# Digitalizaci_n.net
KiCad netlist of a schematic drawn in Altium Designer
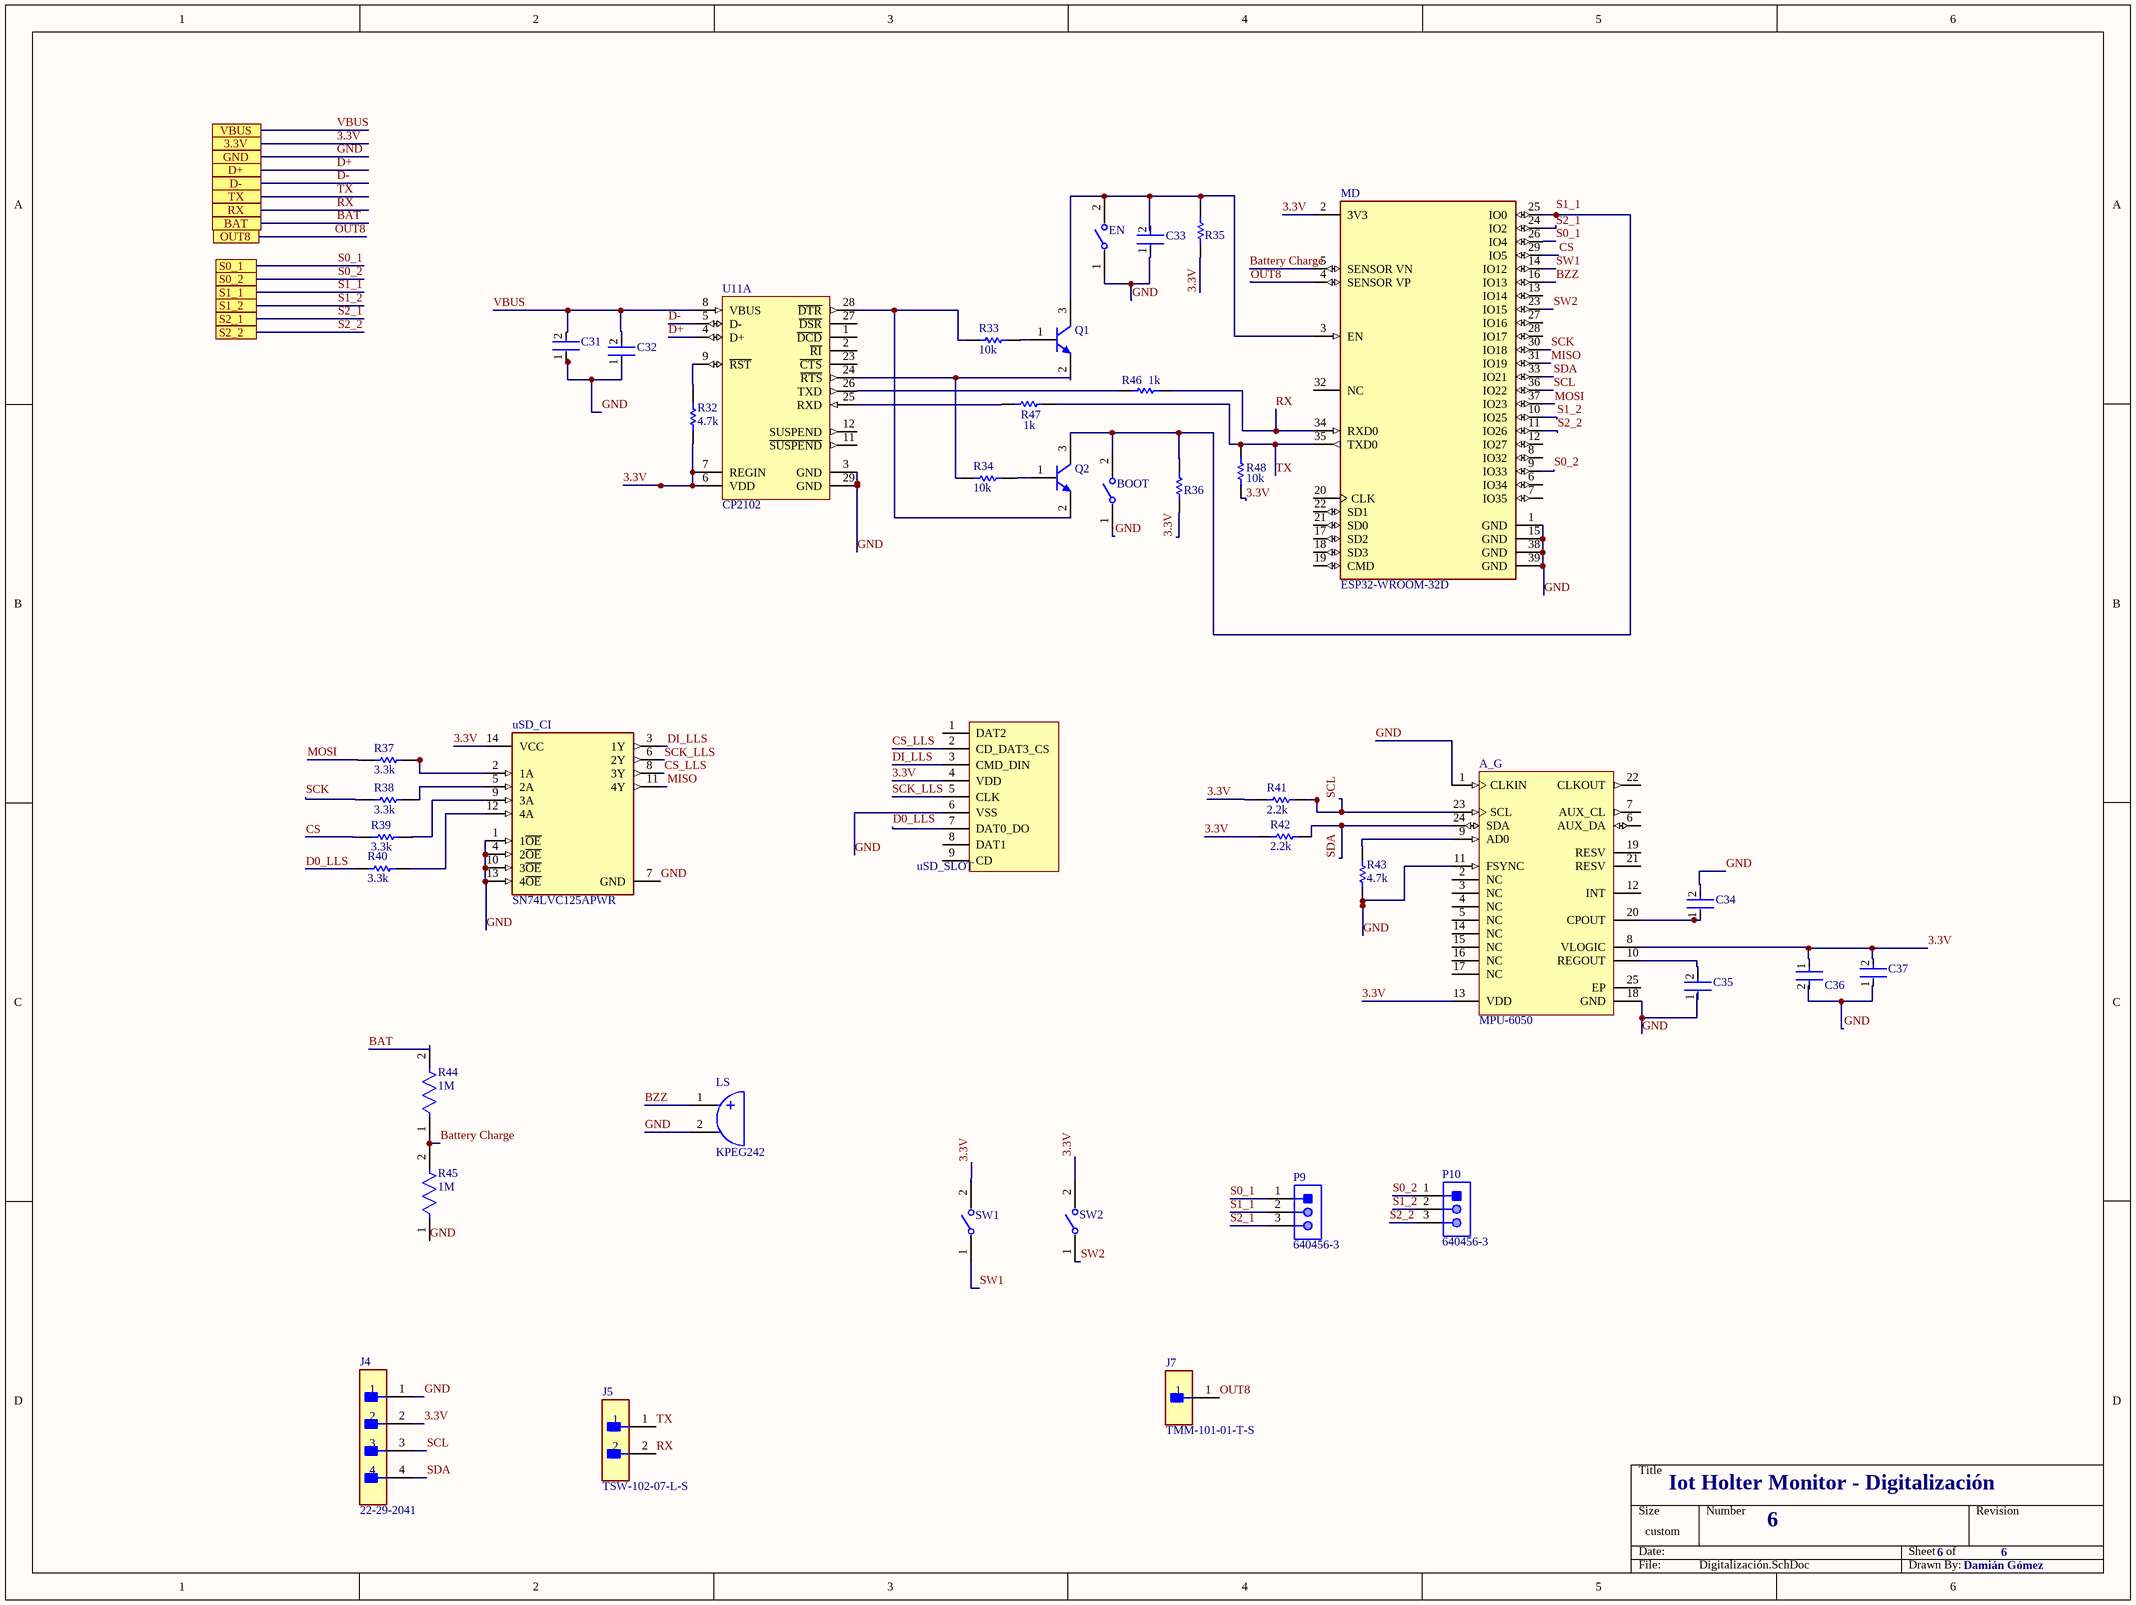
[diagram p0: Digitalización.SchDoc]

(export (version "E")
  (design (tool "Eeschema 10.0.6"))
  (components
    (comp (ref "A_G")
      (value "MPU-6050")
      (footprint "IS-QFN-24_V")
      (fields (field (name "MANUFACTURER") "InvenSense"))
      (libsource (lib "Altium Content Vault") (part "IS-MPU-6050-QFN-24"))
    )
    (comp (ref "BOOT")
      (value "B3U-1000P")
      (footprint "FP-B3U-1000P-MFG")
      (description "SWITCH TACTILE SPST-NO 0.05A 12V")
      (libsource (lib "Altium Content Vault") (part "ae622034201233ca1abcedc05908f33"))
    )
    (comp (ref "C31")
      (value "GRM2165C1H332JA01D")
      (footprint "FP-GRM216-0_1-IPC_B")
      (description "Chip Multilayer Ceramic Capacitors for General Purpose, 0805, 3300pF, C0G, 30ppm/°C, 5%, 50V")
      (fields (field (name "VOLTAGE") "50V") (field (name "TOLERANCE") "5%"))
      (libsource (lib "Altium Content Vault") (part "236180d848d6139a670b325ea6854c9"))
    )
    (comp (ref "C32")
      (value "GRM2165C1H332JA01D")
      (footprint "FP-GRM216-0_1-IPC_B")
      (description "Chip Multilayer Ceramic Capacitors for General Purpose, 0805, 3300pF, C0G, 30ppm/°C, 5%, 50V")
      (fields (field (name "VOLTAGE") "50V") (field (name "TOLERANCE") "5%"))
      (libsource (lib "Altium Content Vault") (part "236180d848d6139a670b325ea6854c9"))
    )
    (comp (ref "C33")
      (value "GRM2165C1H332JA01D")
      (footprint "FP-GRM216-0_1-IPC_B")
      (description "Chip Multilayer Ceramic Capacitors for General Purpose, 0805, 3300pF, C0G, 30ppm/°C, 5%, 50V")
      (fields (field (name "VOLTAGE") "50V") (field (name "TOLERANCE") "5%"))
      (libsource (lib "Altium Content Vault") (part "236180d848d6139a670b325ea6854c9"))
    )
    (comp (ref "C34")
      (value "GRM2165C1H332JA01D")
      (footprint "FP-GRM216-0_1-IPC_B")
      (description "Chip Multilayer Ceramic Capacitors for General Purpose, 0805, 3300pF, C0G, 30ppm/°C, 5%, 50V")
      (fields (field (name "VOLTAGE") "50V") (field (name "TOLERANCE") "5%"))
      (libsource (lib "Altium Content Vault") (part "236180d848d6139a670b325ea6854c9"))
    )
    (comp (ref "C35")
      (value "GRM2165C1H332JA01D")
      (footprint "FP-GRM216-0_1-IPC_B")
      (description "Chip Multilayer Ceramic Capacitors for General Purpose, 0805, 3300pF, C0G, 30ppm/°C, 5%, 50V")
      (fields (field (name "VOLTAGE") "50V") (field (name "TOLERANCE") "5%"))
      (libsource (lib "Altium Content Vault") (part "236180d848d6139a670b325ea6854c9"))
    )
    (comp (ref "C36")
      (value "10uF")
      (footprint "FP-CL31-IPC_C")
      (description "Cap Ceramic 10uF 500V C0G ±5% SMD 1206 +125°C Embossed T/R")
      (fields (field (name "TOLERANCE") "5%"))
      (libsource (lib "Altium Content Vault") (part "b4654b650e69147ec39a6b967a45e02"))
    )
    (comp (ref "C37")
      (value "GRM2165C1H332JA01D")
      (footprint "FP-GRM216-0_1-IPC_B")
      (description "Chip Multilayer Ceramic Capacitors for General Purpose, 0805, 3300pF, C0G, 30ppm/°C, 5%, 50V")
      (fields (field (name "VOLTAGE") "50V") (field (name "TOLERANCE") "5%"))
      (libsource (lib "Altium Content Vault") (part "236180d848d6139a670b325ea6854c9"))
    )
    (comp (ref "EN")
      (value "B3U-1000P")
      (footprint "FP-B3U-1000P-MFG")
      (description "SWITCH TACTILE SPST-NO 0.05A 12V")
      (libsource (lib "Altium Content Vault") (part "ae622034201233ca1abcedc05908f33"))
    )
    (comp (ref "J4")
      (value "22-29-2041")
      (footprint "FP-22-29-2041-MFG")
      (description "CONN HEADER VERT 4POS 2.54MM")
      (libsource (lib "Altium Content Vault") (part "299a8cea1bdcbc3624fe62c390fa72c"))
    )
    (comp (ref "J5")
      (value "TSW-102-07-L-S")
      (footprint "FP-TSW-102-07-L-S-MFG")
      (description "CONN HEADER VERT 2POS 2.54MM")
      (libsource (lib "Altium Content Vault") (part "3bc925449376181038e59eaffc5286c"))
    )
    (comp (ref "J7")
      (value "TMM-101-01-T-S")
      (footprint "FP-TMM-101-01-T-S-MFG")
      (description "CONN HEADER VERT 1POS")
      (libsource (lib "Altium Content Vault") (part "dd45045ce8184df9e99e12baf3f412c"))
    )
    (comp (ref "LS")
      (value "KPEG242")
      (footprint "KINGS-KPEG242-2")
      (description "Piezo Indicator, 4100 Hz, 3 to 16 V, -20 to 70 degC, 2-Pin THD, RoHS")
      (fields (field (name "PARTNUMBER") "KPE-242") (field (name "MANUFACTURER") "KingstateElectronicsCorp."))
      (libsource (lib "Altium Content Vault") (part "KINGS-KPEG242-2"))
    )
    (comp (ref "MD")
      (value "ESP32-WROOM-32D")
      (footprint "FP-ESP32-WROOM-32D-MFG")
      (description "WIFI MODULE 32MBITS SPI FLASH")
      (fields
        (field (name "OCTOPART") "https://octopart.com/esp32-wroom-32d-espressif+systems-91040050")
        (field (name "MANUFACTURER") "Espressif Systems")
      )
      (libsource (lib "Altium Content Vault") (part "a031a76f8c27026a7a7f4657ff233a3"))
    )
    (comp (ref "P9")
      (value "640456-3")
      (footprint "TECO-640456-3")
      (description "Male Header, Pitch 2.54 mm, 1 x 3 Position, Height 10.03 mm, Tail Length 3.56 mm, -55 to 105 degC")
      (fields (field (name "MANUFACTURER") "TE Connectivity"))
      (libsource (lib "Altium Content Vault") (part "CN-1P-M-R3"))
    )
    (comp (ref "P10")
      (value "640456-3")
      (footprint "TECO-640456-3")
      (description "Male Header, Pitch 2.54 mm, 1 x 3 Position, Height 10.03 mm, Tail Length 3.56 mm, -55 to 105 degC")
      (fields (field (name "MANUFACTURER") "TE Connectivity"))
      (libsource (lib "Altium Content Vault") (part "CN-1P-M-R3"))
    )
    (comp (ref "Q1")
      (value "MMBTA42LT1G")
      (footprint "ONSC-SOT-23-3-318-08_V")
      (description "High Voltage Transistor, NPN Silicon, 3-Pin SOT-23, Pb-Free, Tape and Reel")
      (fields (field (name "MANUFACTURER") "On Semiconductor"))
      (libsource (lib "Altium Content Vault") (part "ONSC-NPN-B1E2C3-3"))
    )
    (comp (ref "Q2")
      (value "MMBTA42LT1G")
      (footprint "ONSC-SOT-23-3-318-08_V")
      (description "High Voltage Transistor, NPN Silicon, 3-Pin SOT-23, Pb-Free, Tape and Reel")
      (fields (field (name "MANUFACTURER") "On Semiconductor"))
      (libsource (lib "Altium Content Vault") (part "ONSC-NPN-B1E2C3-3"))
    )
    (comp (ref "R32")
      (value "4.7k")
      (footprint "RESC2013X50X30LL20T20")
      (fields (field (name "MANUFACTURER") "Vishay Dale") (field (name "PART NUMBER") "CRCW08050000Z0EA"))
      (libsource (lib "Altium Content Vault") (part "RES"))
    )
    (comp (ref "R33")
      (value "10k")
      (footprint "RESC2013X50X30LL20T20")
      (fields (field (name "MANUFACTURER") "Vishay Dale") (field (name "PART NUMBER") "CRCW08050000Z0EA"))
      (libsource (lib "Altium Content Vault") (part "RES"))
    )
    (comp (ref "R34")
      (value "10k")
      (footprint "RESC2013X50X30LL20T20")
      (fields (field (name "MANUFACTURER") "Vishay Dale") (field (name "PART NUMBER") "CRCW08050000Z0EA"))
      (libsource (lib "Altium Content Vault") (part "RES"))
    )
    (comp (ref "R35")
      (value "10k")
      (footprint "RESC2013X50X30LL20T20")
      (fields (field (name "MANUFACTURER") "Vishay Dale") (field (name "PART NUMBER") "CRCW08050000Z0EA"))
      (libsource (lib "Altium Content Vault") (part "RES"))
    )
    (comp (ref "R36")
      (value "10k")
      (footprint "RESC2013X50X30LL20T20")
      (fields (field (name "MANUFACTURER") "Vishay Dale") (field (name "PART NUMBER") "CRCW08050000Z0EA"))
      (libsource (lib "Altium Content Vault") (part "RES"))
    )
    (comp (ref "R37")
      (value "3.3k")
      (footprint "RESC2013X50X30LL20T20")
      (fields (field (name "MANUFACTURER") "Vishay Dale") (field (name "PART NUMBER") "CRCW08050000Z0EA"))
      (libsource (lib "Altium Content Vault") (part "RES"))
    )
    (comp (ref "R38")
      (value "3.3k")
      (footprint "RESC2013X50X30LL20T20")
      (fields (field (name "MANUFACTURER") "Vishay Dale") (field (name "PART NUMBER") "CRCW08050000Z0EA"))
      (libsource (lib "Altium Content Vault") (part "RES"))
    )
    (comp (ref "R39")
      (value "3.3k")
      (footprint "RESC2013X50X30LL20T20")
      (fields (field (name "MANUFACTURER") "Vishay Dale") (field (name "PART NUMBER") "CRCW08050000Z0EA"))
      (libsource (lib "Altium Content Vault") (part "RES"))
    )
    (comp (ref "R40")
      (value "3.3k")
      (footprint "RESC2013X50X30LL20T20")
      (fields (field (name "MANUFACTURER") "Vishay Dale") (field (name "PART NUMBER") "CRCW08050000Z0EA"))
      (libsource (lib "Altium Content Vault") (part "RES"))
    )
    (comp (ref "R41")
      (value "2.2k")
      (footprint "RESC2013X50X30LL20T20")
      (fields (field (name "MANUFACTURER") "Vishay Dale") (field (name "PART NUMBER") "CRCW08050000Z0EA"))
      (libsource (lib "Altium Content Vault") (part "RES"))
    )
    (comp (ref "R42")
      (value "2.2k")
      (footprint "RESC2013X50X30LL20T20")
      (fields (field (name "MANUFACTURER") "Vishay Dale") (field (name "PART NUMBER") "CRCW08050000Z0EA"))
      (libsource (lib "Altium Content Vault") (part "RES"))
    )
    (comp (ref "R43")
      (value "4.7k")
      (footprint "RESC2013X50X30LL20T20")
      (fields (field (name "MANUFACTURER") "Vishay Dale") (field (name "PART NUMBER") "CRCW08050000Z0EA"))
      (libsource (lib "Altium Content Vault") (part "RES"))
    )
    (comp (ref "R44")
      (value "1M")
      (footprint "FP-RC3216-MFG")
      (description "Res Thick Film 1206 20kΩ 5% 0.25W ±100ppm/°C Molded SMD T/R")
      (fields (field (name "TOLERANCE") "5%"))
      (libsource (lib "Altium Content Vault") (part "1029c3af85768c4190bb7ad29bc67b5"))
    )
    (comp (ref "R45")
      (value "1M")
      (footprint "FP-RC3216-MFG")
      (description "Res Thick Film 1206 20kΩ 5% 0.25W ±100ppm/°C Molded SMD T/R")
      (fields (field (name "TOLERANCE") "5%"))
      (libsource (lib "Altium Content Vault") (part "1029c3af85768c4190bb7ad29bc67b5"))
    )
    (comp (ref "R46")
      (value "1k")
      (footprint "RESC2013X50X30LL20T20")
      (fields (field (name "MANUFACTURER") "Vishay Dale") (field (name "PART NUMBER") "CRCW08050000Z0EA"))
      (libsource (lib "Altium Content Vault") (part "RES"))
    )
    (comp (ref "R47")
      (value "1k")
      (footprint "RESC2013X50X30LL20T20")
      (fields (field (name "MANUFACTURER") "Vishay Dale") (field (name "PART NUMBER") "CRCW08050000Z0EA"))
      (libsource (lib "Altium Content Vault") (part "RES"))
    )
    (comp (ref "R48")
      (value "10k")
      (footprint "RESC2013X50X30LL20T20")
      (fields (field (name "MANUFACTURER") "Vishay Dale") (field (name "PART NUMBER") "CRCW08050000Z0EA"))
      (libsource (lib "Altium Content Vault") (part "RES"))
    )
    (comp (ref "SW1")
      (value "B3U-1000P")
      (footprint "FP-B3U-1000P-MFG")
      (description "SWITCH TACTILE SPST-NO 0.05A 12V")
      (libsource (lib "Altium Content Vault") (part "ae622034201233ca1abcedc05908f33"))
    )
    (comp (ref "SW2")
      (value "B3U-1000P")
      (footprint "FP-B3U-1000P-MFG")
      (description "SWITCH TACTILE SPST-NO 0.05A 12V")
      (libsource (lib "Altium Content Vault") (part "ae622034201233ca1abcedc05908f33"))
    )
    (comp (ref "U11")
      (value "CP2102")
      (footprint "SLAB-QFN-28-3125x3125TP_M")
      (description "Single-Chip USB to URAT Bridge, 3.3 V, -40 to 85 degC, 28-Pin QFN, RoHS, Tape and Reel")
      (fields (field (name "MANUFACTURER") "Silicon Labs"))
      (libsource (lib "Altium Content Vault") (part "SLAB-CP210X-QFN-28-29"))
    )
    (comp (ref "uSD_CI")
      (value "SN74LVC125APWR")
      (footprint "FP-PW0014A-IPC_B")
      (description "IC BUF NON-INVERT 3.6V 14TSSOP")
      (libsource (lib "Altium Content Vault") (part "0c185306b27c65c3e4a0d950f37c68a"))
    )
    (comp (ref "uSD_SLOT")
      (value "uSD_TFP09-2-12BComponent_1")
      (footprint "TF09-2-12B")
      (libsource (lib "uSD_TFP09-2-12B") (part "uSD_TFP09-2-12BComponent_1"))
    )
  )
  (nets
    (net (code "1") (name "/3.3V") (class "Default")
      (node (ref "A_G") (pin "13") (pinfunction "VDD_13") (pintype "power_in"))
      (node (ref "A_G") (pin "8") (pinfunction "VLOGIC_8") (pintype "power_in"))
      (node (ref "C36") (pin "1") (pinfunction "1_1") (pintype "passive"))
      (node (ref "C37") (pin "2") (pinfunction "2_2") (pintype "passive"))
      (node (ref "J4") (pin "2") (pinfunction "2_2") (pintype "passive"))
      (node (ref "MD") (pin "2") (pinfunction "3V3_2") (pintype "power_in"))
      (node (ref "R32") (pin "1") (pinfunction "1_1") (pintype "passive"))
      (node (ref "R35") (pin "1") (pinfunction "1_1") (pintype "passive"))
      (node (ref "R36") (pin "1") (pinfunction "1_1") (pintype "passive"))
      (node (ref "R41") (pin "1") (pinfunction "1_1") (pintype "passive"))
      (node (ref "R42") (pin "1") (pinfunction "1_1") (pintype "passive"))
      (node (ref "R48") (pin "1") (pinfunction "1_1") (pintype "passive"))
      (node (ref "SW1") (pin "2") (pinfunction "2_2") (pintype "passive"))
      (node (ref "SW2") (pin "2") (pinfunction "2_2") (pintype "passive"))
      (node (ref "U11") (pin "6") (pinfunction "VDD_6") (pintype "power_in"))
      (node (ref "U11") (pin "7") (pinfunction "REGIN_7") (pintype "power_in"))
      (node (ref "uSD_CI") (pin "14") (pinfunction "VCC_14") (pintype "power_in"))
      (node (ref "uSD_SLOT") (pin "4") (pinfunction "VDD_4") (pintype "passive"))
    )
    (net (code "2") (name "/BAT") (class "Default")
      (node (ref "R44") (pin "2") (pinfunction "2_2") (pintype "passive"))
    )
    (net (code "3") (name "/BZZ") (class "Default")
      (node (ref "LS") (pin "1") (pinfunction "1_1") (pintype "passive"))
      (node (ref "MD") (pin "16") (pinfunction "IO13_16") (pintype "bidirectional"))
    )
    (net (code "4") (name "/Battery Charge") (class "Default")
      (node (ref "MD") (pin "5") (pinfunction "SENSOR_VN_5") (pintype "bidirectional"))
      (node (ref "R44") (pin "1") (pinfunction "1_1") (pintype "passive"))
      (node (ref "R45") (pin "2") (pinfunction "2_2") (pintype "passive"))
    )
    (net (code "5") (name "/CS") (class "Default")
      (node (ref "MD") (pin "29") (pinfunction "IO5_29") (pintype "bidirectional"))
      (node (ref "R39") (pin "1") (pinfunction "1_1") (pintype "passive"))
    )
    (net (code "6") (name "/CS_LLS") (class "Default")
      (node (ref "uSD_CI") (pin "8") (pinfunction "3Y_8") (pintype "output"))
      (node (ref "uSD_SLOT") (pin "2") (pinfunction "CD_DAT3_CS_2") (pintype "passive"))
    )
    (net (code "7") (name "/D+") (class "Default")
      (node (ref "U11") (pin "4") (pinfunction "D+_4") (pintype "bidirectional"))
    )
    (net (code "8") (name "/D-") (class "Default")
      (node (ref "U11") (pin "5") (pinfunction "D-_5") (pintype "bidirectional"))
    )
    (net (code "9") (name "/D0_LLS") (class "Default")
      (node (ref "R40") (pin "1") (pinfunction "1_1") (pintype "passive"))
      (node (ref "uSD_SLOT") (pin "7") (pinfunction "DAT0_DO_7") (pintype "passive"))
    )
    (net (code "10") (name "/DI_LLS") (class "Default")
      (node (ref "uSD_CI") (pin "3") (pinfunction "1Y_3") (pintype "output"))
      (node (ref "uSD_SLOT") (pin "3") (pinfunction "CMD_DIN_3") (pintype "passive"))
    )
    (net (code "11") (name "/GND") (class "Default")
      (node (ref "A_G") (pin "1") (pinfunction "CLKIN_1") (pintype "input"))
      (node (ref "A_G") (pin "11") (pinfunction "FSYNC_11") (pintype "input"))
      (node (ref "A_G") (pin "18") (pinfunction "GND_18") (pintype "passive"))
      (node (ref "BOOT") (pin "1") (pinfunction "1_1") (pintype "passive"))
      (node (ref "C31") (pin "1") (pinfunction "1_1") (pintype "passive"))
      (node (ref "C32") (pin "1") (pinfunction "1_1") (pintype "passive"))
      (node (ref "C33") (pin "1") (pinfunction "1_1") (pintype "passive"))
      (node (ref "C34") (pin "2") (pinfunction "2_2") (pintype "passive"))
      (node (ref "C35") (pin "1") (pinfunction "1_1") (pintype "passive"))
      (node (ref "C36") (pin "2") (pinfunction "2_2") (pintype "passive"))
      (node (ref "C37") (pin "1") (pinfunction "1_1") (pintype "passive"))
      (node (ref "EN") (pin "1") (pinfunction "1_1") (pintype "passive"))
      (node (ref "J4") (pin "1") (pinfunction "1_1") (pintype "passive"))
      (node (ref "LS") (pin "2") (pinfunction "2_2") (pintype "passive"))
      (node (ref "MD") (pin "1") (pinfunction "GND_1") (pintype "passive"))
      (node (ref "MD") (pin "15") (pinfunction "GND_15") (pintype "passive"))
      (node (ref "MD") (pin "38") (pinfunction "GND_38") (pintype "passive"))
      (node (ref "MD") (pin "39") (pinfunction "GND_39") (pintype "passive"))
      (node (ref "R43") (pin "1") (pinfunction "1_1") (pintype "passive"))
      (node (ref "R45") (pin "1") (pinfunction "1_1") (pintype "passive"))
      (node (ref "U11") (pin "29") (pinfunction "GND_29") (pintype "passive"))
      (node (ref "U11") (pin "3") (pinfunction "GND_3") (pintype "passive"))
      (node (ref "uSD_CI") (pin "1") (pinfunction "1~{OE}_1") (pintype "input"))
      (node (ref "uSD_CI") (pin "10") (pinfunction "3~{OE}_10") (pintype "input"))
      (node (ref "uSD_CI") (pin "13") (pinfunction "4~{OE}_13") (pintype "input"))
      (node (ref "uSD_CI") (pin "4") (pinfunction "2~{OE}_4") (pintype "input"))
      (node (ref "uSD_CI") (pin "7") (pinfunction "GND_7") (pintype "passive"))
      (node (ref "uSD_SLOT") (pin "6") (pinfunction "VSS_6") (pintype "passive"))
    )
    (net (code "12") (name "/MISO") (class "Default")
      (node (ref "MD") (pin "31") (pinfunction "IO19_31") (pintype "bidirectional"))
      (node (ref "uSD_CI") (pin "11") (pinfunction "4Y_11") (pintype "output"))
    )
    (net (code "13") (name "/MOSI") (class "Default")
      (node (ref "MD") (pin "37") (pinfunction "IO23_37") (pintype "bidirectional"))
      (node (ref "R37") (pin "1") (pinfunction "1_1") (pintype "passive"))
    )
    (net (code "14") (name "/OUT8") (class "Default")
      (node (ref "J7") (pin "1") (pinfunction "1_1") (pintype "passive"))
      (node (ref "MD") (pin "4") (pinfunction "SENSOR_VP_4") (pintype "bidirectional"))
    )
    (net (code "15") (name "/RX") (class "Default")
      (node (ref "J5") (pin "2") (pinfunction "2_2") (pintype "passive"))
      (node (ref "MD") (pin "34") (pinfunction "RXD0_34") (pintype "input"))
      (node (ref "R46") (pin "2") (pinfunction "2_2") (pintype "passive"))
    )
    (net (code "16") (name "/S0_1") (class "Default")
      (node (ref "MD") (pin "26") (pinfunction "IO4_26") (pintype "bidirectional"))
      (node (ref "P9") (pin "1") (pinfunction "1_1") (pintype "passive"))
    )
    (net (code "17") (name "/S0_2") (class "Default")
      (node (ref "MD") (pin "9") (pinfunction "IO33_9") (pintype "bidirectional"))
      (node (ref "P10") (pin "1") (pinfunction "1_1") (pintype "passive"))
    )
    (net (code "18") (name "/S1_1") (class "Default")
      (node (ref "BOOT") (pin "2") (pinfunction "2_2") (pintype "passive"))
      (node (ref "MD") (pin "25") (pinfunction "IO0_25") (pintype "bidirectional"))
      (node (ref "P9") (pin "2") (pinfunction "2_2") (pintype "passive"))
      (node (ref "Q2") (pin "3") (pinfunction "C_3") (pintype "passive"))
      (node (ref "R36") (pin "2") (pinfunction "2_2") (pintype "passive"))
    )
    (net (code "19") (name "/S1_2") (class "Default")
      (node (ref "MD") (pin "10") (pinfunction "IO25_10") (pintype "bidirectional"))
      (node (ref "P10") (pin "2") (pinfunction "2_2") (pintype "passive"))
    )
    (net (code "20") (name "/S2_1") (class "Default")
      (node (ref "MD") (pin "24") (pinfunction "IO2_24") (pintype "bidirectional"))
      (node (ref "P9") (pin "3") (pinfunction "3_3") (pintype "passive"))
    )
    (net (code "21") (name "/S2_2") (class "Default")
      (node (ref "MD") (pin "11") (pinfunction "IO26_11") (pintype "bidirectional"))
      (node (ref "P10") (pin "3") (pinfunction "3_3") (pintype "passive"))
    )
    (net (code "22") (name "/SCK") (class "Default")
      (node (ref "MD") (pin "30") (pinfunction "IO18_30") (pintype "bidirectional"))
      (node (ref "R38") (pin "1") (pinfunction "1_1") (pintype "passive"))
    )
    (net (code "23") (name "/SCK_LLS") (class "Default")
      (node (ref "uSD_CI") (pin "6") (pinfunction "2Y_6") (pintype "output"))
      (node (ref "uSD_SLOT") (pin "5") (pinfunction "CLK_5") (pintype "passive"))
    )
    (net (code "24") (name "/SCL") (class "Default")
      (node (ref "A_G") (pin "23") (pinfunction "SCL_23") (pintype "input"))
      (node (ref "J4") (pin "3") (pinfunction "3_3") (pintype "passive"))
      (node (ref "MD") (pin "36") (pinfunction "IO22_36") (pintype "bidirectional"))
      (node (ref "R41") (pin "2") (pinfunction "2_2") (pintype "passive"))
    )
    (net (code "25") (name "/SDA") (class "Default")
      (node (ref "A_G") (pin "24") (pinfunction "SDA_24") (pintype "bidirectional"))
      (node (ref "J4") (pin "4") (pinfunction "4_4") (pintype "passive"))
      (node (ref "MD") (pin "33") (pinfunction "IO21_33") (pintype "bidirectional"))
      (node (ref "R42") (pin "2") (pinfunction "2_2") (pintype "passive"))
    )
    (net (code "26") (name "/SW1") (class "Default")
      (node (ref "MD") (pin "14") (pinfunction "IO12_14") (pintype "bidirectional"))
      (node (ref "SW1") (pin "1") (pinfunction "1_1") (pintype "passive"))
    )
    (net (code "27") (name "/SW2") (class "Default")
      (node (ref "MD") (pin "23") (pinfunction "IO15_23") (pintype "bidirectional"))
      (node (ref "SW2") (pin "1") (pinfunction "1_1") (pintype "passive"))
    )
    (net (code "28") (name "/TX") (class "Default")
      (node (ref "J5") (pin "1") (pinfunction "1_1") (pintype "passive"))
      (node (ref "MD") (pin "35") (pinfunction "TXD0_35") (pintype "output"))
      (node (ref "R47") (pin "2") (pinfunction "2_2") (pintype "passive"))
      (node (ref "R48") (pin "2") (pinfunction "2_2") (pintype "passive"))
    )
    (net (code "29") (name "/VBUS") (class "Default")
      (node (ref "C31") (pin "2") (pinfunction "2_2") (pintype "passive"))
      (node (ref "C32") (pin "2") (pinfunction "2_2") (pintype "passive"))
      (node (ref "U11") (pin "8") (pinfunction "VBUS_8") (pintype "input"))
    )
    (net (code "30") (name "Net-(A_G-AD0)") (class "Default")
      (node (ref "A_G") (pin "9") (pinfunction "AD0_9") (pintype "input"))
      (node (ref "R43") (pin "2") (pinfunction "2_2") (pintype "passive"))
    )
    (net (code "31") (name "Net-(A_G-CPOUT)") (class "Default")
      (node (ref "A_G") (pin "20") (pinfunction "CPOUT_20") (pintype "passive"))
      (node (ref "C34") (pin "1") (pinfunction "1_1") (pintype "passive"))
    )
    (net (code "32") (name "Net-(A_G-REGOUT)") (class "Default")
      (node (ref "A_G") (pin "10") (pinfunction "REGOUT_10") (pintype "passive"))
      (node (ref "C35") (pin "2") (pinfunction "2_2") (pintype "passive"))
    )
    (net (code "33") (name "Net-(MD-EN)") (class "Default")
      (node (ref "C33") (pin "2") (pinfunction "2_2") (pintype "passive"))
      (node (ref "EN") (pin "2") (pinfunction "2_2") (pintype "passive"))
      (node (ref "MD") (pin "3") (pinfunction "EN_3") (pintype "input"))
      (node (ref "Q1") (pin "3") (pinfunction "C_3") (pintype "passive"))
      (node (ref "R35") (pin "2") (pinfunction "2_2") (pintype "passive"))
    )
    (net (code "34") (name "Net-(Q1-B)") (class "Default")
      (node (ref "Q1") (pin "1") (pinfunction "B_1") (pintype "passive"))
      (node (ref "R33") (pin "2") (pinfunction "2_2") (pintype "passive"))
    )
    (net (code "35") (name "Net-(Q1-E)") (class "Default")
      (node (ref "Q1") (pin "2") (pinfunction "E_2") (pintype "passive"))
      (node (ref "R34") (pin "1") (pinfunction "1_1") (pintype "passive"))
      (node (ref "U11") (pin "24") (pinfunction "~{RTS}_24") (pintype "output"))
    )
    (net (code "36") (name "Net-(Q2-B)") (class "Default")
      (node (ref "Q2") (pin "1") (pinfunction "B_1") (pintype "passive"))
      (node (ref "R34") (pin "2") (pinfunction "2_2") (pintype "passive"))
    )
    (net (code "37") (name "Net-(Q2-E)") (class "Default")
      (node (ref "Q2") (pin "2") (pinfunction "E_2") (pintype "passive"))
      (node (ref "R33") (pin "1") (pinfunction "1_1") (pintype "passive"))
      (node (ref "U11") (pin "28") (pinfunction "~{DTR}_28") (pintype "output"))
    )
    (net (code "38") (name "Net-(U11A-RXD)") (class "Default")
      (node (ref "R47") (pin "1") (pinfunction "1_1") (pintype "passive"))
      (node (ref "U11") (pin "25") (pinfunction "RXD_25") (pintype "input"))
    )
    (net (code "39") (name "Net-(U11A-TXD)") (class "Default")
      (node (ref "R46") (pin "1") (pinfunction "1_1") (pintype "passive"))
      (node (ref "U11") (pin "26") (pinfunction "TXD_26") (pintype "output"))
    )
    (net (code "40") (name "Net-(U11A-~{RST})") (class "Default")
      (node (ref "R32") (pin "2") (pinfunction "2_2") (pintype "passive"))
      (node (ref "U11") (pin "9") (pinfunction "~{RST}_9") (pintype "bidirectional"))
    )
    (net (code "41") (name "Net-(uSD_CI-1A)") (class "Default")
      (node (ref "R37") (pin "2") (pinfunction "2_2") (pintype "passive"))
      (node (ref "uSD_CI") (pin "2") (pinfunction "1A_2") (pintype "input"))
    )
    (net (code "42") (name "Net-(uSD_CI-2A)") (class "Default")
      (node (ref "R38") (pin "2") (pinfunction "2_2") (pintype "passive"))
      (node (ref "uSD_CI") (pin "5") (pinfunction "2A_5") (pintype "input"))
    )
    (net (code "43") (name "Net-(uSD_CI-3A)") (class "Default")
      (node (ref "R39") (pin "2") (pinfunction "2_2") (pintype "passive"))
      (node (ref "uSD_CI") (pin "9") (pinfunction "3A_9") (pintype "input"))
    )
    (net (code "44") (name "Net-(uSD_CI-4A)") (class "Default")
      (node (ref "R40") (pin "2") (pinfunction "2_2") (pintype "passive"))
      (node (ref "uSD_CI") (pin "12") (pinfunction "4A_12") (pintype "input"))
    )
    (net (code "45") (name "unconnected-(A_G-AUX_CL-Pad7)") (class "Default")
      (node (ref "A_G") (pin "7") (pinfunction "AUX_CL_7") (pintype "output"))
    )
    (net (code "46") (name "unconnected-(A_G-AUX_DA-Pad6)") (class "Default")
      (node (ref "A_G") (pin "6") (pinfunction "AUX_DA_6") (pintype "bidirectional"))
    )
    (net (code "47") (name "unconnected-(A_G-CLKOUT-Pad22)") (class "Default")
      (node (ref "A_G") (pin "22") (pinfunction "CLKOUT_22") (pintype "output"))
    )
    (net (code "48") (name "unconnected-(A_G-EP-Pad25)") (class "Default")
      (node (ref "A_G") (pin "25") (pinfunction "EP_25") (pintype "power_in"))
    )
    (net (code "49") (name "unconnected-(A_G-INT-Pad12)") (class "Default")
      (node (ref "A_G") (pin "12") (pinfunction "INT_12") (pintype "open_collector"))
    )
    (net (code "50") (name "unconnected-(A_G-NC-Pad2)") (class "Default")
      (node (ref "A_G") (pin "2") (pinfunction "NC_2") (pintype "passive"))
    )
    (net (code "51") (name "unconnected-(A_G-NC-Pad3)") (class "Default")
      (node (ref "A_G") (pin "3") (pinfunction "NC_3") (pintype "passive"))
    )
    (net (code "52") (name "unconnected-(A_G-NC-Pad4)") (class "Default")
      (node (ref "A_G") (pin "4") (pinfunction "NC_4") (pintype "passive"))
    )
    (net (code "53") (name "unconnected-(A_G-NC-Pad5)") (class "Default")
      (node (ref "A_G") (pin "5") (pinfunction "NC_5") (pintype "passive"))
    )
    (net (code "54") (name "unconnected-(A_G-NC-Pad14)") (class "Default")
      (node (ref "A_G") (pin "14") (pinfunction "NC_14") (pintype "passive"))
    )
    (net (code "55") (name "unconnected-(A_G-NC-Pad15)") (class "Default")
      (node (ref "A_G") (pin "15") (pinfunction "NC_15") (pintype "passive"))
    )
    (net (code "56") (name "unconnected-(A_G-NC-Pad16)") (class "Default")
      (node (ref "A_G") (pin "16") (pinfunction "NC_16") (pintype "passive"))
    )
    (net (code "57") (name "unconnected-(A_G-NC-Pad17)") (class "Default")
      (node (ref "A_G") (pin "17") (pinfunction "NC_17") (pintype "passive"))
    )
    (net (code "58") (name "unconnected-(A_G-RESV-Pad19)") (class "Default")
      (node (ref "A_G") (pin "19") (pinfunction "RESV_19") (pintype "passive"))
    )
    (net (code "59") (name "unconnected-(A_G-RESV-Pad21)") (class "Default")
      (node (ref "A_G") (pin "21") (pinfunction "RESV_21") (pintype "passive"))
    )
    (net (code "60") (name "unconnected-(MD-CLK-Pad20)") (class "Default")
      (node (ref "MD") (pin "20") (pinfunction "CLK_20") (pintype "tri_state"))
    )
    (net (code "61") (name "unconnected-(MD-CMD-Pad19)") (class "Default")
      (node (ref "MD") (pin "19") (pinfunction "CMD_19") (pintype "bidirectional"))
    )
    (net (code "62") (name "unconnected-(MD-IO14-Pad13)") (class "Default")
      (node (ref "MD") (pin "13") (pinfunction "IO14_13") (pintype "bidirectional"))
    )
    (net (code "63") (name "unconnected-(MD-IO16-Pad27)") (class "Default")
      (node (ref "MD") (pin "27") (pinfunction "IO16_27") (pintype "bidirectional"))
    )
    (net (code "64") (name "unconnected-(MD-IO17-Pad28)") (class "Default")
      (node (ref "MD") (pin "28") (pinfunction "IO17_28") (pintype "bidirectional"))
    )
    (net (code "65") (name "unconnected-(MD-IO27-Pad12)") (class "Default")
      (node (ref "MD") (pin "12") (pinfunction "IO27_12") (pintype "bidirectional"))
    )
    (net (code "66") (name "unconnected-(MD-IO32-Pad8)") (class "Default")
      (node (ref "MD") (pin "8") (pinfunction "IO32_8") (pintype "bidirectional"))
    )
    (net (code "67") (name "unconnected-(MD-IO34-Pad6)") (class "Default")
      (node (ref "MD") (pin "6") (pinfunction "IO34_6") (pintype "bidirectional"))
    )
    (net (code "68") (name "unconnected-(MD-IO35-Pad7)") (class "Default")
      (node (ref "MD") (pin "7") (pinfunction "IO35_7") (pintype "bidirectional"))
    )
    (net (code "69") (name "unconnected-(MD-NC-Pad32)") (class "Default")
      (node (ref "MD") (pin "32") (pinfunction "NC_32") (pintype "passive"))
    )
    (net (code "70") (name "unconnected-(MD-SD0-Pad21)") (class "Default")
      (node (ref "MD") (pin "21") (pinfunction "SD0_21") (pintype "bidirectional"))
    )
    (net (code "71") (name "unconnected-(MD-SD1-Pad22)") (class "Default")
      (node (ref "MD") (pin "22") (pinfunction "SD1_22") (pintype "bidirectional"))
    )
    (net (code "72") (name "unconnected-(MD-SD2-Pad17)") (class "Default")
      (node (ref "MD") (pin "17") (pinfunction "SD2_17") (pintype "bidirectional"))
    )
    (net (code "73") (name "unconnected-(MD-SD3-Pad18)") (class "Default")
      (node (ref "MD") (pin "18") (pinfunction "SD3_18") (pintype "bidirectional"))
    )
    (net (code "74") (name "unconnected-(U11A-SUSPEND-Pad12)") (class "Default")
      (node (ref "U11") (pin "12") (pinfunction "SUSPEND_12") (pintype "output"))
    )
    (net (code "75") (name "unconnected-(U11A-~{CTS}-Pad23)") (class "Default")
      (node (ref "U11") (pin "23") (pinfunction "~{CTS}_23") (pintype "tri_state"))
    )
    (net (code "76") (name "unconnected-(U11A-~{DCD}-Pad1)") (class "Default")
      (node (ref "U11") (pin "1") (pinfunction "~{DCD}_1") (pintype "tri_state"))
    )
    (net (code "77") (name "unconnected-(U11A-~{DSR}-Pad27)") (class "Default")
      (node (ref "U11") (pin "27") (pinfunction "~{DSR}_27") (pintype "tri_state"))
    )
    (net (code "78") (name "unconnected-(U11A-~{RI}-Pad2)") (class "Default")
      (node (ref "U11") (pin "2") (pinfunction "~{RI}_2") (pintype "tri_state"))
    )
    (net (code "79") (name "unconnected-(U11A-~{SUSPEND}-Pad11)") (class "Default")
      (node (ref "U11") (pin "11") (pinfunction "~{SUSPEND}_11") (pintype "output"))
    )
    (net (code "80") (name "unconnected-(uSD_SLOT-CD-Pad9)") (class "Default")
      (node (ref "uSD_SLOT") (pin "9") (pinfunction "CD_9") (pintype "passive"))
    )
    (net (code "81") (name "unconnected-(uSD_SLOT-DAT1-Pad8)") (class "Default")
      (node (ref "uSD_SLOT") (pin "8") (pinfunction "DAT1_8") (pintype "passive"))
    )
    (net (code "82") (name "unconnected-(uSD_SLOT-DAT2-Pad1)") (class "Default")
      (node (ref "uSD_SLOT") (pin "1") (pinfunction "DAT2_1") (pintype "passive"))
    )
  )
)
